# BACKPMAN30_Intfs.net
KiCad netlist of a schematic drawn in Altium Designer
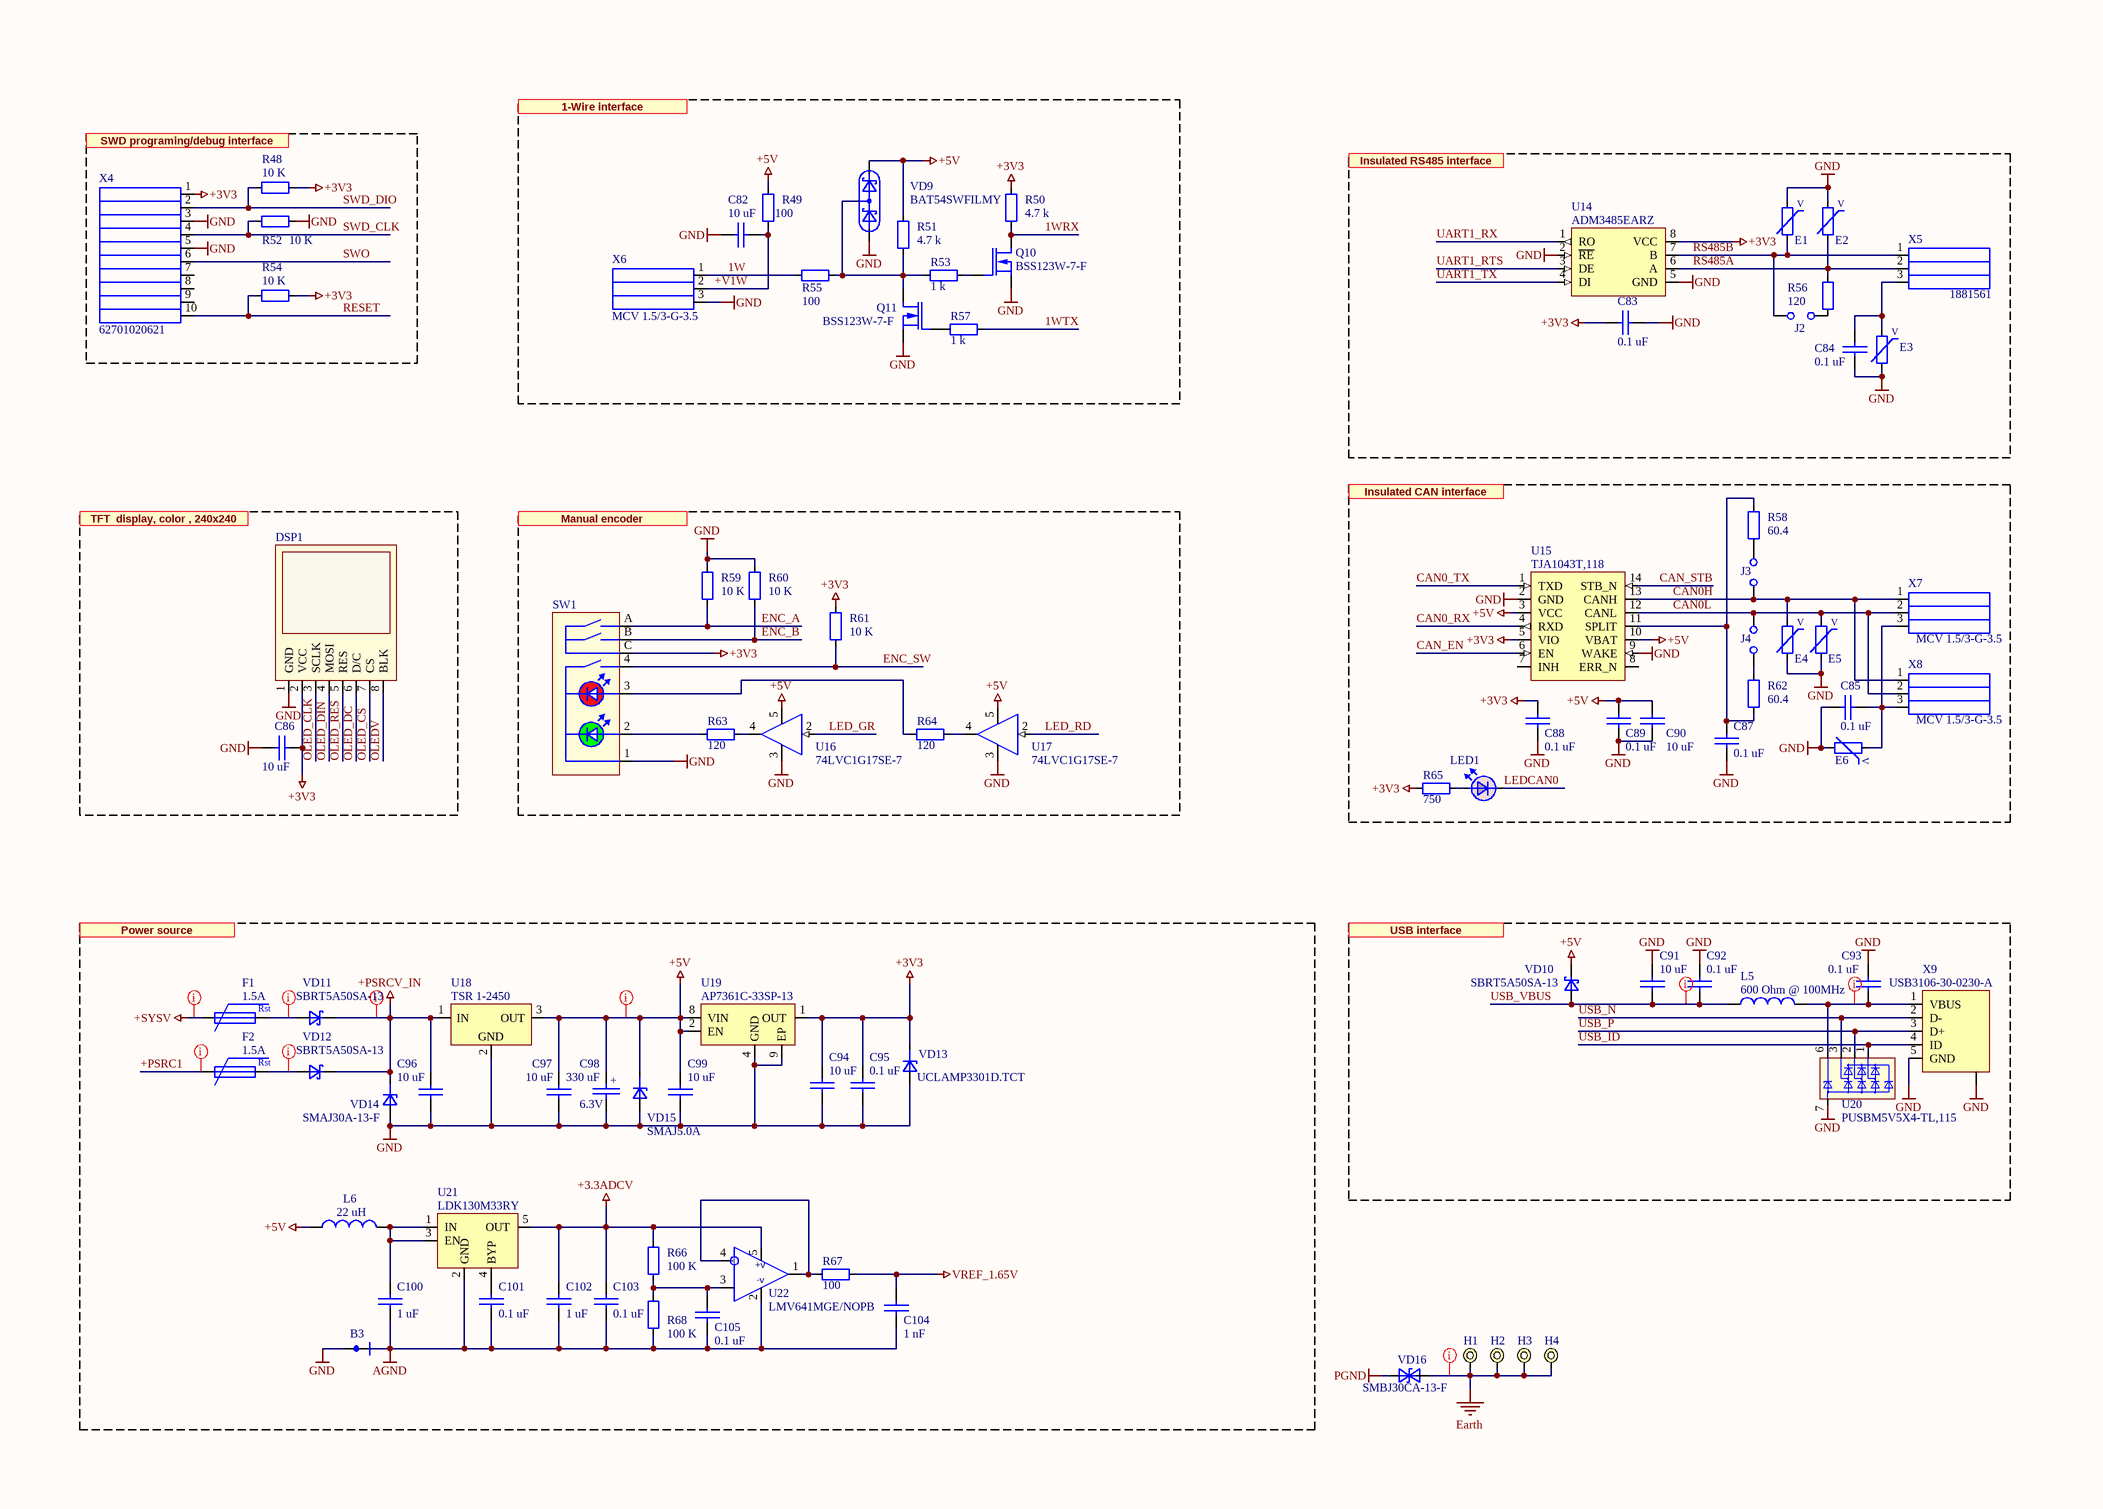
[diagram p0: BACKPMAN30_Intfs.SchDoc]

(export (version "E")
  (design (tool "Eeschema 10.0.6"))
  (components
    (comp (ref "B3")
      (value "Net tie 0.3mm")
      (footprint "Net tee 0.3 mm")
      (libsource (lib "ea_Mechanical") (part "Net tie 0.3mm"))
    )
    (comp (ref "C82")
      (value "10 uF")
      (footprint "2012[0805]")
      (description "10 µF ±10%, 25V, Ceramic Capacitor X5R 0805 (2012 Metric),  -55°C ~ 85°C")
      (fields (field (name "MANUFACTURER") "Murata Electronics") (field (name "TOLERANCE") "±10%"))
      (libsource (lib "ea_Capacitors_0805") (part "GRM21BR61E106KA73L"))
    )
    (comp (ref "C83")
      (value "0.1 uF")
      (footprint "1608[0603]")
      (description "0.1 µF ±10% 50V Ceramic Capacitor X7R 0603 (1608 Metric), -55°C ~ 125°C")
      (fields
        (field (name "MANUFACTURER") "Walsin Technology Corporation")
        (field (name "PARTNUM") "1292-1643-1-ND")
      )
      (libsource (lib "ea_Capacitors_0603") (part "0603B104K500CT"))
    )
    (comp (ref "C84")
      (value "0.1 uF")
      (footprint "1608[0603]")
      (description "0.1 µF ±10% 50V Ceramic Capacitor X7R 0603 (1608 Metric), -55°C ~ 125°C")
      (fields
        (field (name "TOLERANCE") "+-10%")
        (field (name "MANUFACTURER") "Walsin Technology Corporation")
      )
      (libsource (lib "ea_Capacitors_0603") (part "0603B104K500CT"))
    )
    (comp (ref "C85")
      (value "0.1 uF")
      (footprint "1608[0603]")
      (description "0.1 µF ±10% 50V Ceramic Capacitor X7R 0603 (1608 Metric), -55°C ~ 125°C")
      (fields
        (field (name "TOLERANCE") "+-10%")
        (field (name "MANUFACTURER") "Walsin Technology Corporation")
      )
      (libsource (lib "ea_Capacitors_0603") (part "0603B104K500CT"))
    )
    (comp (ref "C86")
      (value "10 uF")
      (footprint "2012[0805]")
      (description "10 µF ±10%, 25V, Ceramic Capacitor X5R 0805 (2012 Metric),  -55°C ~ 85°C")
      (fields (field (name "MANUFACTURER") "Murata Electronics") (field (name "TOLERANCE") "±10%"))
      (libsource (lib "ea_Capacitors_0805") (part "GRM21BR61E106KA73L"))
    )
    (comp (ref "C87")
      (value "0.1 uF")
      (footprint "1608[0603]")
      (description "0.1 µF ±10% 50V Ceramic Capacitor X7R 0603 (1608 Metric), -55°C ~ 125°C")
      (fields
        (field (name "TOLERANCE") "+-10%")
        (field (name "MANUFACTURER") "Walsin Technology Corporation")
      )
      (libsource (lib "ea_Capacitors_0603") (part "0603B104K500CT"))
    )
    (comp (ref "C88")
      (value "0.1 uF")
      (footprint "1608[0603]")
      (description "0.1 µF ±10% 50V Ceramic Capacitor X7R 0603 (1608 Metric), -55°C ~ 125°C")
      (fields
        (field (name "TOLERANCE") "+-10%")
        (field (name "MANUFACTURER") "Walsin Technology Corporation")
      )
      (libsource (lib "ea_Capacitors_0603") (part "0603B104K500CT"))
    )
    (comp (ref "C89")
      (value "0.1 uF")
      (footprint "1608[0603]")
      (description "0.1 µF ±10% 50V Ceramic Capacitor X7R 0603 (1608 Metric), -55°C ~ 125°C")
      (fields
        (field (name "TOLERANCE") "+-10%")
        (field (name "MANUFACTURER") "Walsin Technology Corporation")
      )
      (libsource (lib "ea_Capacitors_0603") (part "0603B104K500CT"))
    )
    (comp (ref "C90")
      (value "10 uF")
      (footprint "2012[0805]")
      (description "10 µF ±10%, 25V, Ceramic Capacitor X5R 0805 (2012 Metric),  -55°C ~ 85°C")
      (fields (field (name "MANUFACTURER") "Murata Electronics") (field (name "TOLERANCE") "±10%"))
      (libsource (lib "ea_Capacitors_0805") (part "GRM21BR61E106KA73L"))
    )
    (comp (ref "C91")
      (value "10 uF")
      (footprint "2012[0805]")
      (description "10 µF ±10%, 25V, Ceramic Capacitor X5R 0805 (2012 Metric),  -55°C ~ 85°C")
      (fields (field (name "MANUFACTURER") "Murata Electronics") (field (name "TOLERANCE") "±10%"))
      (libsource (lib "ea_Capacitors_0805") (part "GRM21BR61E106KA73L"))
    )
    (comp (ref "C92")
      (value "0.1 uF")
      (footprint "1608[0603]")
      (description "0.1 µF ±10% 50V Ceramic Capacitor X7R 0603 (1608 Metric), -55°C ~ 125°C")
      (fields
        (field (name "TOLERANCE") "+-10%")
        (field (name "MANUFACTURER") "Walsin Technology Corporation")
      )
      (libsource (lib "ea_Capacitors_0603") (part "0603B104K500CT"))
    )
    (comp (ref "C93")
      (value "0.1 uF")
      (footprint "1608[0603]")
      (description "0.1 µF ±10% 50V Ceramic Capacitor X7R 0603 (1608 Metric), -55°C ~ 125°C")
      (fields
        (field (name "TOLERANCE") "+-10%")
        (field (name "MANUFACTURER") "Walsin Technology Corporation")
      )
      (libsource (lib "ea_Capacitors_0603") (part "0603B104K500CT"))
    )
    (comp (ref "C94")
      (value "10 uF")
      (footprint "2012[0805]")
      (description "10 µF ±10%, 25V, Ceramic Capacitor X5R 0805 (2012 Metric),  -55°C ~ 85°C")
      (fields (field (name "MANUFACTURER") "Murata Electronics") (field (name "TOLERANCE") "±10%"))
      (libsource (lib "ea_Capacitors_0805") (part "GRM21BR61E106KA73L"))
    )
    (comp (ref "C95")
      (value "0.1 uF")
      (footprint "1608[0603]")
      (description "0.1 µF ±10% 50V Ceramic Capacitor X7R 0603 (1608 Metric), -55°C ~ 125°C")
      (fields
        (field (name "TOLERANCE") "+-10%")
        (field (name "MANUFACTURER") "Walsin Technology Corporation")
      )
      (libsource (lib "ea_Capacitors_0603") (part "0603B104K500CT"))
    )
    (comp (ref "C96")
      (value "10 uF")
      (footprint "3225[1210]")
      (description "10 µF ±10%, 50V, Ceramic Capacitor X7R, 1210 (3225 Metric), -55°C ~ 125°C")
      (fields
        (field (name "MANUFACTURER") "CAL-CHIP ELECTRONICS, INC.")
        (field (name "PARTNUM") "2571-GMC32X7R106K50NTTR-ND")
      )
      (libsource (lib "ea_Capacitors_1210") (part "GMC32X7R106K50NT"))
    )
    (comp (ref "C97")
      (value "10 uF")
      (footprint "2012[0805]")
      (description "10 µF ±10%, 25V, Ceramic Capacitor X5R 0805 (2012 Metric),  -55°C ~ 85°C")
      (fields (field (name "MANUFACTURER") "Murata Electronics") (field (name "TOLERANCE") "±10%"))
      (libsource (lib "ea_Capacitors_0805") (part "GRM21BR61E106KA73L"))
    )
    (comp (ref "C98")
      (value "330 uF")
      (footprint "T495 D")
      (description "330 µF Molded Tantalum Capacitors 6.3 V 2917 (7343 Metric) 100mOhm, -55°C ~ 125°C")
      (fields
        (field (name "MANUFACTURER") "KEMET")
        (field (name "TOLERANCE") "±10%")
        (field (name "VOLTAGE") "6.3V")
      )
      (libsource (lib "ea_Capacitors") (part "T495D337K006ATE100"))
    )
    (comp (ref "C99")
      (value "10 uF")
      (footprint "2012[0805]")
      (description "10 µF ±10%, 25V, Ceramic Capacitor X5R 0805 (2012 Metric),  -55°C ~ 85°C")
      (fields (field (name "MANUFACTURER") "Murata Electronics") (field (name "TOLERANCE") "±10%"))
      (libsource (lib "ea_Capacitors_0805") (part "GRM21BR61E106KA73L"))
    )
    (comp (ref "C100")
      (value "1 uF")
      (footprint "1608[0603]")
      (description "1 uF, ±10%, Low ESL, 50V, Ceramic Capacitor X5R 0603 (1608 Metric), -55°C ~ 85°C")
      (fields (field (name "MANUFACTURER") "Venkel") (field (name "PARTNUM") "445-7468-1-ND"))
      (libsource (lib "ea_Capacitors_0603") (part "C1608X5R1H105K080AB"))
    )
    (comp (ref "C101")
      (value "0.1 uF")
      (footprint "1608[0603]")
      (description "0.1 µF ±10% 50V Ceramic Capacitor X7R 0603 (1608 Metric), -55°C ~ 125°C")
      (fields
        (field (name "MANUFACTURER") "Walsin Technology Corporation")
        (field (name "PARTNUM") "1292-1643-1-ND")
      )
      (libsource (lib "ea_Capacitors_0603") (part "0603B104K500CT"))
    )
    (comp (ref "C102")
      (value "1 uF")
      (footprint "1608[0603]")
      (description "1 uF, ±10%, Low ESL, 50V, Ceramic Capacitor X5R 0603 (1608 Metric), -55°C ~ 85°C")
      (fields (field (name "MANUFACTURER") "Venkel") (field (name "PARTNUM") "445-7468-1-ND"))
      (libsource (lib "ea_Capacitors_0603") (part "C1608X5R1H105K080AB"))
    )
    (comp (ref "C103")
      (value "0.1 uF")
      (footprint "1608[0603]")
      (description "0.1 µF ±10% 50V Ceramic Capacitor X7R 0603 (1608 Metric), -55°C ~ 125°C")
      (fields
        (field (name "MANUFACTURER") "Walsin Technology Corporation")
        (field (name "PARTNUM") "1292-1643-1-ND")
      )
      (libsource (lib "ea_Capacitors_0603") (part "0603B104K500CT"))
    )
    (comp (ref "C104")
      (value "1 nF")
      (footprint "0603 CAP")
      (description "1000pF, ±5%, 50V, X7R, 0603 (1608 Metric), -55°C ~ 125°C, -, General Purpose")
      (fields (field (name "PART NUMBER") "CC0603JRX7R9BB102") (field (name "MANUFACTURER") "Yageo"))
      (libsource (lib "ea_PassivComps") (part "Capacitor"))
    )
    (comp (ref "C105")
      (value "0.1 uF")
      (footprint "1608[0603]")
      (description "0.1 µF ±10% 50V Ceramic Capacitor X7R 0603 (1608 Metric), -55°C ~ 125°C")
      (fields
        (field (name "MANUFACTURER") "Walsin Technology Corporation")
        (field (name "PARTNUM") "1292-1643-1-ND")
      )
      (libsource (lib "ea_Capacitors_0603") (part "0603B104K500CT"))
    )
    (comp (ref "DSP1")
      (value "1.54_inch_IPS_Module")
      (footprint "1.54 inch IPS 240x240")
      (fields (field (name "PARTNUM") "MSP1541"))
      (libsource (lib "ea_LCD") (part "1.54_inch_IPS_Module"))
    )
    (comp (ref "E1")
      (value "ESD03A5V5R17V")
      (footprint "0603")
      (description "Low and Ultra Low Capacitance ESD Suppressor, Voperating=5.5V, Vclamp=17V, < 1nS,1nA, 0603,")
      (fields
        (field (name "MANUFACTURER") "Stackpole Electronics Inc")
        (field (name "PARTNUM") "ESD03A5V5R17VCT-ND")
      )
      (libsource (lib "") (part "ESD03A5V5R17V_1"))
    )
    (comp (ref "E2")
      (value "ESD03A5V5R17V")
      (footprint "0603")
      (description "Low and Ultra Low Capacitance ESD Suppressor, Voperating=5.5V, Vclamp=17V, < 1nS,1nA, 0603,")
      (fields
        (field (name "MANUFACTURER") "Stackpole Electronics Inc")
        (field (name "PARTNUM") "ESD03A5V5R17VCT-ND")
      )
      (libsource (lib "") (part "ESD03A5V5R17V_1"))
    )
    (comp (ref "E3")
      (value "823 560 505 60")
      (footprint "0603")
      (description "Low and Ultra Low Capacitance ESD Suppressor, Voperating=5.5V, Vclamp=17V, < 1nS,1nA, 0603,")
      (fields
        (field (name "MANUFACTURER") "Stackpole Electronics Inc")
        (field (name "PARTNUM") "ESD03A5V5R17VCT-ND")
      )
      (libsource (lib "") (part "ESD03A5V5R17V_1"))
    )
    (comp (ref "E4")
      (value "ESD03A5V5R17V")
      (footprint "0603")
      (description "Low and Ultra Low Capacitance ESD Suppressor, Voperating=5.5V, Vclamp=17V, < 1nS,1nA, 0603,")
      (fields
        (field (name "MANUFACTURER") "Stackpole Electronics Inc")
        (field (name "PARTNUM") "ESD03A5V5R17VCT-ND")
      )
      (libsource (lib "") (part "ESD03A5V5R17V_1"))
    )
    (comp (ref "E5")
      (value "ESD03A5V5R17V")
      (footprint "0603")
      (description "Low and Ultra Low Capacitance ESD Suppressor, Voperating=5.5V, Vclamp=17V, < 1nS,1nA, 0603,")
      (fields
        (field (name "MANUFACTURER") "Stackpole Electronics Inc")
        (field (name "PARTNUM") "ESD03A5V5R17VCT-ND")
      )
      (libsource (lib "") (part "ESD03A5V5R17V_1"))
    )
    (comp (ref "E6")
      (value "ESD03A5V5R17V")
      (footprint "0603")
      (description "Low and Ultra Low Capacitance ESD Suppressor, Voperating=5.5V, Vclamp=17V, < 1nS,1nA, 0603,")
      (fields
        (field (name "MANUFACTURER") "Stackpole Electronics Inc")
        (field (name "PARTNUM") "ESD03A5V5R17VCT-ND")
      )
      (libsource (lib "ea_TVS_protection") (part "ESD03A5V5R17V"))
    )
    (comp (ref "F1")
      (value "1.5A")
      (footprint "2920 (7351 Metric)")
      (description "PTC RESETTABLE 60V 750MA, It=1.5A, 0.3s 2920(7351)")
      (fields (field (name "MANUFACTURER") "Bel Fuse Inc.") (field (name "PARTNUM") "507-1743-1-ND"))
      (libsource (lib "ea_Fuses") (part "0ZCF0075AF2C"))
    )
    (comp (ref "F2")
      (value "1.5A")
      (footprint "2920 (7351 Metric)")
      (description "PTC RESETTABLE 60V 750MA, It=1.5A, 0.3s 2920(7351)")
      (fields (field (name "MANUFACTURER") "Bel Fuse Inc.") (field (name "PARTNUM") "507-1743-1-ND"))
      (libsource (lib "ea_Fuses") (part "0ZCF0075AF2C"))
    )
    (comp (ref "H1")
      (value "Hole 5MM Plated")
      (footprint "HOLE_5MM plated")
      (libsource (lib "ea_Mechanical") (part "Hole 5MM Plated"))
    )
    (comp (ref "H2")
      (value "Hole 5MM Plated")
      (footprint "HOLE_5MM plated")
      (libsource (lib "ea_Mechanical") (part "Hole 5MM Plated"))
    )
    (comp (ref "H3")
      (value "Hole 5MM Plated")
      (footprint "HOLE_5MM plated")
      (libsource (lib "ea_Mechanical") (part "Hole 5MM Plated"))
    )
    (comp (ref "H4")
      (value "Hole 5MM Plated")
      (footprint "HOLE_5MM plated")
      (libsource (lib "ea_Mechanical") (part "Hole 5MM Plated"))
    )
    (comp (ref "J2")
      (value "PH1-02-TA-HT")
      (footprint "HDR1X2V")
      (description "Connector Header Through Hole 2 position 0.100\" (2.54mm), Contact Length - Mating 6 mm")
      (fields (field (name "MANUFACTURER") "Adam Tech") (field (name "PARTNUM") "2057-PH1-02-UA-ND"))
      (libsource (lib "ea_Commutation") (part "PH1-02-UA"))
    )
    (comp (ref "J3")
      (value "PH1-02-TA-HT")
      (footprint "HDR1X2V")
      (description "Connector Header Through Hole 2 position 0.100\" (2.54mm), Contact Length - Mating 6 mm")
      (fields (field (name "MANUFACTURER") "Adam Tech") (field (name "PARTNUM") "2057-PH1-02-UA-ND"))
      (libsource (lib "ea_Commutation") (part "PH1-02-UA"))
    )
    (comp (ref "J4")
      (value "PH1-02-TA-HT")
      (footprint "HDR1X2V")
      (description "Connector Header Through Hole 2 position 0.100\" (2.54mm), Contact Length - Mating 6 mm")
      (fields (field (name "MANUFACTURER") "Adam Tech") (field (name "PARTNUM") "2057-PH1-02-UA-ND"))
      (libsource (lib "ea_Commutation") (part "PH1-02-UA"))
    )
    (comp (ref "L5")
      (value "600 Ohm @ 100MHz")
      (footprint "0805")
      (description "FERRITE BEAD 600 OHM, 0805, -55°C ~ 125°C")
      (fields (field (name "MANUFACTURER") "TDK Corporation") (field (name "PARTNUM") "445-2206-1-ND"))
      (libsource (lib "ea_Inductors") (part "MPZ2012S601AT000"))
    )
    (comp (ref "L6")
      (value "22 uH")
      (footprint "2518")
      (description "22 µH Unshielded Wirewound Inductor, 490 mA, 560mOhm, 1007 (2518 Metric)")
      (fields (field (name "MANUFACTURER") "Taiyo Yuden") (field (name "PARTNUM") "587-2439-1-ND"))
      (libsource (lib "ea_Inductors") (part "BRC2518T220K"))
    )
    (comp (ref "LED1")
      (value "SML-211UTT86")
      (footprint "0805 LED")
      (description "0805 red LED, hibright, 2 mA, 1.8V, 130°")
      (fields (field (name "MANUFACTURER") "Rohm") (field (name "PARTNUM") "511-1292-1-ND"))
      (libsource (lib "ea_Indicators") (part "SML-211UTT86"))
    )
    (comp (ref "Q10")
      (value "BSS123W-7-F")
      (footprint "SOT323-3")
      (description "MOSFETs N-CH, 2V @ 1mA, 6 Ohm @ 170mA, 10V, 170mA, 100V, SOT-323,  -55°C ~ 150°C")
      (fields (field (name "MANUFACTURER") "Diodes Incorporated") (field (name "PARTNUM") "BSS123W-FDICT-ND"))
      (libsource (lib "") (part "BSS123W-7-F_1"))
    )
    (comp (ref "Q11")
      (value "BSS123W-7-F")
      (footprint "SOT323-3")
      (description "MOSFETs N-CH, 2V @ 1mA, 6 Ohm @ 170mA, 10V, 170mA, 100V, SOT-323,  -55°C ~ 150°C")
      (fields (field (name "MANUFACTURER") "Diodes Incorporated") (field (name "PARTNUM") "BSS123W-FDICT-ND"))
      (libsource (lib "ea_Transistors") (part "BSS123W-7-F"))
    )
    (comp (ref "R48")
      (value "10 K")
      (footprint "0603")
      (fields
        (field (name "MANUFACTURER") "Stackpole Electronics Inc")
        (field (name "TOLERANCE") "1%")
        (field (name "PARTNUM") "RMCF0603FT10K0CT-ND")
      )
      (libsource (lib "ea_Resistors_0603") (part "RMCF0603FT10K0"))
    )
    (comp (ref "R49")
      (value "100")
      (footprint "0603")
      (fields
        (field (name "MANUFACTURER") "Stackpole Electronics Inc.")
        (field (name "TOLERANCE") "±1%")
        (field (name "VOLTAGE") "75V")
      )
      (libsource (lib "ea_PassivComps") (part "Resistor"))
    )
    (comp (ref "R50")
      (value "4.7 k")
      (footprint "0603")
      (fields
        (field (name "MANUFACTURER") "Stackpole Electronics Inc.")
        (field (name "TOLERANCE") "±1%")
        (field (name "VOLTAGE") "75V")
      )
      (libsource (lib "") (part "Resistor_1"))
    )
    (comp (ref "R51")
      (value "4.7 k")
      (footprint "0603")
      (fields
        (field (name "MANUFACTURER") "Stackpole Electronics Inc.")
        (field (name "TOLERANCE") "±1%")
        (field (name "VOLTAGE") "75V")
      )
      (libsource (lib "") (part "Resistor_1"))
    )
    (comp (ref "R52")
      (value "10 K")
      (footprint "0603")
      (fields
        (field (name "MANUFACTURER") "Stackpole Electronics Inc")
        (field (name "TOLERANCE") "1%")
        (field (name "PARTNUM") "RMCF0603FT10K0CT-ND")
      )
      (libsource (lib "ea_Resistors_0603") (part "RMCF0603FT10K0"))
    )
    (comp (ref "R53")
      (value "1 k")
      (footprint "0603")
      (fields
        (field (name "MANUFACTURER") "Stackpole Electronics Inc.")
        (field (name "TOLERANCE") "±1%")
        (field (name "VOLTAGE") "75V")
      )
      (libsource (lib "") (part "Resistor_2"))
    )
    (comp (ref "R54")
      (value "10 K")
      (footprint "0603")
      (fields
        (field (name "MANUFACTURER") "Stackpole Electronics Inc")
        (field (name "TOLERANCE") "1%")
        (field (name "PARTNUM") "RMCF0603FT10K0CT-ND")
      )
      (libsource (lib "ea_Resistors_0603") (part "RMCF0603FT10K0"))
    )
    (comp (ref "R55")
      (value "100")
      (footprint "0603")
      (fields
        (field (name "MANUFACTURER") "Stackpole Electronics Inc.")
        (field (name "TOLERANCE") "±1%")
        (field (name "VOLTAGE") "75V")
      )
      (libsource (lib "") (part "Resistor_3"))
    )
    (comp (ref "R56")
      (value "120")
      (footprint "0603")
      (fields
        (field (name "MANUFACTURER") "Stackpole Electronics Inc.")
        (field (name "TOLERANCE") "±1%")
        (field (name "VOLTAGE") "75V")
      )
      (libsource (lib "ea_PassivComps") (part "Resistor"))
    )
    (comp (ref "R57")
      (value "1 k")
      (footprint "0603")
      (fields
        (field (name "MANUFACTURER") "Stackpole Electronics Inc.")
        (field (name "TOLERANCE") "±1%")
        (field (name "VOLTAGE") "75V")
      )
      (libsource (lib "") (part "Resistor_2"))
    )
    (comp (ref "R58")
      (value "60.4")
      (footprint "0603")
      (fields
        (field (name "MANUFACTURER") "Vishay Dale")
        (field (name "TOLERANCE") "±1%")
        (field (name "VOLTAGE") "75V")
      )
      (libsource (lib "ea_PassivComps") (part "Resistor"))
    )
    (comp (ref "R59")
      (value "10 K")
      (footprint "0603")
      (fields
        (field (name "MANUFACTURER") "Stackpole Electronics Inc")
        (field (name "TOLERANCE") "1%")
        (field (name "PARTNUM") "RMCF0603FT10K0CT-ND")
      )
      (libsource (lib "") (part "RMCF0603FT10K0_1"))
    )
    (comp (ref "R60")
      (value "10 K")
      (footprint "0603")
      (fields
        (field (name "MANUFACTURER") "Stackpole Electronics Inc")
        (field (name "TOLERANCE") "1%")
        (field (name "PARTNUM") "RMCF0603FT10K0CT-ND")
      )
      (libsource (lib "") (part "RMCF0603FT10K0_1"))
    )
    (comp (ref "R61")
      (value "10 K")
      (footprint "0603")
      (fields
        (field (name "MANUFACTURER") "Stackpole Electronics Inc")
        (field (name "TOLERANCE") "1%")
        (field (name "PARTNUM") "RMCF0603FT10K0CT-ND")
      )
      (libsource (lib "") (part "RMCF0603FT10K0_1"))
    )
    (comp (ref "R62")
      (value "60.4")
      (footprint "0603")
      (fields
        (field (name "MANUFACTURER") "Vishay Dale")
        (field (name "TOLERANCE") "±1%")
        (field (name "VOLTAGE") "75V")
      )
      (libsource (lib "ea_PassivComps") (part "Resistor"))
    )
    (comp (ref "R63")
      (value "120")
      (footprint "0603")
      (fields
        (field (name "MANUFACTURER") "Stackpole Electronics Inc.")
        (field (name "TOLERANCE") "±1%")
        (field (name "VOLTAGE") "75V")
      )
      (libsource (lib "") (part "Resistor_2"))
    )
    (comp (ref "R64")
      (value "120")
      (footprint "0603")
      (fields
        (field (name "MANUFACTURER") "Stackpole Electronics Inc.")
        (field (name "TOLERANCE") "±1%")
        (field (name "VOLTAGE") "75V")
      )
      (libsource (lib "") (part "Resistor_2"))
    )
    (comp (ref "R65")
      (value "750")
      (footprint "0603")
      (fields
        (field (name "MANUFACTURER") "Stackpole Electronics Inc.")
        (field (name "TOLERANCE") "±1%")
        (field (name "VOLTAGE") "75V")
      )
      (libsource (lib "") (part "Resistor_2"))
    )
    (comp (ref "R66")
      (value "100 K")
      (footprint "0603")
      (fields
        (field (name "MANUFACTURER") "Susumu")
        (field (name "TOLERANCE") "±0.05%")
        (field (name "PARTNUM") "RG16N100KWCT-ND")
      )
      (libsource (lib "ea_Resistors_0603") (part "RG1608N-104-W-T1"))
    )
    (comp (ref "R67")
      (value "100")
      (footprint "0603")
      (fields
        (field (name "MANUFACTURER") "Stackpole Electronics Inc.")
        (field (name "TOLERANCE") "±1%")
        (field (name "VOLTAGE") "75V")
      )
      (libsource (lib "") (part "Resistor_2"))
    )
    (comp (ref "R68")
      (value "100 K")
      (footprint "0603")
      (fields
        (field (name "MANUFACTURER") "Susumu")
        (field (name "TOLERANCE") "±0.05%")
        (field (name "PARTNUM") "RG16N100KWCT-ND")
      )
      (libsource (lib "ea_Resistors_0603") (part "RG1608N-104-W-T1"))
    )
    (comp (ref "SW1")
      (value "PEL12D-4225S-S2024")
      (footprint "PEL12D-4225S-S2024")
      (description "Rotary Encoder Mechanical 24 Quadrature (Incremental) Vertical")
      (fields (field (name "MANUFACTURER") "Bourns Inc.") (field (name "PARTNUM") "PEL12D-4225S-S2024-ND"))
      (libsource (lib "ea_Commutation") (part "PEL12D-4225S-S2024"))
    )
    (comp (ref "U14")
      (value "ADM3485EARZ")
      (footprint "SO-8")
      (description "1/1 Transceiver Half RS422, RS485, VCC 3.3 V,  8-SOIC, -40°C ~ 85°C")
      (fields (field (name "MANUFACTURER") "Analog Devices") (field (name "PARTNUM") "584-ADM3485EARZ-R7"))
      (libsource (lib "ea_IC_Interfaces") (part "ADM3485EARZ"))
    )
    (comp (ref "U15")
      (value "TJA1043T,118")
      (footprint "SOT108-1")
      (description "1/1 Transceiver Half CANbus, 5Mbps, 4.5-5.5V, 3V IO,  14-SO, -40°C ~ 150°C")
      (fields (field (name "MANUFACTURER") "NXP") (field (name "PARTNUM") "2776120RL"))
      (libsource (lib "ea_IC_Interfaces") (part "TJA1043T,118"))
    )
    (comp (ref "U16")
      (value "74LVC1G17SE-7")
      (footprint "SOT-353 ON Semi")
      (description "IC SGL SCHMITT BUFFER SOT353")
      (fields
        (field (name "MANUFACTURER") "Diodes Incorporated")
        (field (name "PARTNUM") "74LVC1G17SE-7CT-ND")
      )
      (libsource (lib "ea_IC_Logic") (part "74LVC1G17SE-7"))
    )
    (comp (ref "U17")
      (value "74LVC1G17SE-7")
      (footprint "SOT-353 ON Semi")
      (description "IC SGL SCHMITT BUFFER SOT353")
      (fields
        (field (name "MANUFACTURER") "Diodes Incorporated")
        (field (name "PARTNUM") "74LVC1G17SE-7CT-ND")
      )
      (libsource (lib "ea_IC_Logic") (part "74LVC1G17SE-7"))
    )
    (comp (ref "U18")
      (value "TSR 1-2450")
      (footprint "TSR 1 Traco Power")
      (description "Linear Regulator Replacement DC DC Converter 5W, 5V, 1A, 6.5V - 36V Input, -40°C ~ 85°C")
      (fields (field (name "MANUFACTURER") "Traco Power") (field (name "PARTNUM") "1951-2747-ND"))
      (libsource (lib "ea_IC_Power_Reg_Ref_Sw") (part "TSR 1-2450"))
    )
    (comp (ref "U19")
      (value "AP7361C-33SP-13")
      (footprint "SOIC-8 EDP")
      (description "LDO, 3.3 V, 1A, 0.36V@1A, Vin=6V max, -40..+85C, 8-SO-EP")
      (fields
        (field (name "PARTNUM") "AP7361C-33SP-13DICT-ND")
        (field (name "MANUFACTURER") "Diodes Incorporated")
      )
      (libsource (lib "ea_IC_Power_Reg_Ref_Sw") (part "AP7361C-33SP-13"))
    )
    (comp (ref "U20")
      (value "PUSBM5V5X4-TL,115")
      (footprint "DFN1616-6")
      (description "TVS DIODE 5.5VWM 12VC 6HXSON")
      (fields (field (name "MANUFACTURER") "NXP Semiconductors") (field (name "PARTNUM") "568-10921-1-ND"))
      (libsource (lib "ea_TVS_protection") (part "PUSBM5V5X4-TL,115"))
    )
    (comp (ref "U21")
      (value "LDK130M33RY")
      (footprint "SOT23-5")
      (description "LDO 3.3 V, 250 mA, Vin < 5.5V, Iq < 12uA, -40..+125 C, SOT23-5")
      (fields (field (name "MANUFACTURER") "STMicroelectronics") (field (name "PARTNUM") "511-LDK130M33RY"))
      (libsource (lib "ea_IC_Power_Reg_Ref_Sw") (part "LDK130M33RY"))
    )
    (comp (ref "U22")
      (value "LMV641MGE/NOPB")
      (footprint "SOT-353 ON Semi")
      (description "OpAmp,  Rail-to-Rail,  10MHz, VSS 2.7V ~ 12V, Vofs 30µV,  SC-70-5, -40°C ~ 125°C")
      (fields
        (field (name "MANUFACTURER") "Texas Instruments")
        (field (name "PARTNUM") "LMV641MGE/NOPBCT-ND")
      )
      (libsource (lib "ea_IC_OPAmps_AnComparators") (part "LMV641MGE/NOPB"))
    )
    (comp (ref "VD9")
      (value "BAT54SWFILMY")
      (footprint "SOT323-3")
      (description "Series Shottky Diodes array, 40V, 300 mA, SOT-323, -40°C...150°C")
      (fields (field (name "MANUFACTURER") "STMicroelectronics") (field (name "PARTNUM") "497-17757-1-ND"))
      (libsource (lib "ea_Diodes") (part "BAT54SWFILMY"))
    )
    (comp (ref "VD10")
      (value "SBRT5A50SA-13")
      (footprint "SMA")
      (description "Schottky Power Rectifier 3A, 40V, SMA")
      (fields
        (field (name "MANUFACTURER") "Diodes Incorporated")
        (field (name "PARTNUM") "SBRT5A50SA-13DICT-ND")
      )
      (libsource (lib "ea_Diodes") (part "SBRT5A50SA-13"))
    )
    (comp (ref "VD11")
      (value "SBRT5A50SA-13")
      (footprint "SMA")
      (description "Schottky Power Rectifier 3A, 40V, SMA")
      (fields
        (field (name "MANUFACTURER") "Diodes Incorporated")
        (field (name "PARTNUM") "SBRT5A50SA-13DICT-ND")
      )
      (libsource (lib "ea_Diodes") (part "SBRT5A50SA-13"))
    )
    (comp (ref "VD12")
      (value "SBRT5A50SA-13")
      (footprint "SMA")
      (description "Schottky Power Rectifier 3A, 40V, SMA")
      (fields
        (field (name "MANUFACTURER") "Diodes Incorporated")
        (field (name "PARTNUM") "SBRT5A50SA-13DICT-ND")
      )
      (libsource (lib "ea_Diodes") (part "SBRT5A50SA-13"))
    )
    (comp (ref "VD13")
      (value "UCLAMP3301D.TCT")
      (footprint "SOD-323")
      (description "TVS 3.3V (Max), Vbr=3.5V, 9.5V Clamp 10A (8/20µs) Ipp Tvs Diode Surface Mount SOD-323")
      (fields (field (name "MANUFACTURER") "Semtech Corporation") (field (name "PARTNUM") "UCLAMP3301DCT-ND"))
      (libsource (lib "ea_TVS_protection") (part "UCLAMP3301D.TCT"))
    )
    (comp (ref "VD14")
      (value "SMAJ30A-13-F")
      (footprint "SMA")
      (description "48.4V Clamp 8.3A Ipp Tvs Diode Surface Mount SMA,")
      (fields (field (name "MANUFACTURER") "Diodes Incorporated") (field (name "PARTNUM") "SMAJ30A-FDICT-ND"))
      (libsource (lib "ea_TVS_protection") (part "SMAJ30A-13-F"))
    )
    (comp (ref "VD15")
      (value "SMAJ5.0A")
      (footprint "SMA")
      (description "9.2V Clamp 43.5A Ipp Tvs Diode Surface Mount SMA, -55°C ~ 150°C (TJ)")
      (fields (field (name "MANUFACTURER") "Littelfuse Inc.") (field (name "PARTNUM") "SMAJ5.0ALFCT-ND"))
      (libsource (lib "ea_TVS_protection") (part "SMAJ5.0A"))
    )
    (comp (ref "VD16")
      (value "SMBJ30CA-13-F")
      (footprint "DO-214AA_SMBJ BI")
      (description "TVS 600W, Vbr=33.3V, Vcl=48.4V,  Bidirectional, SMB, -55°C ~ 150°C")
      (fields
        (field (name "MANUFACTURER") "Diodes Incorporated")
        (field (name "PARTNUM") "SMBJ30CA-FDICT-ND")
      )
      (libsource (lib "ea_TVS_protection") (part "SMBJ30CA-13-F"))
    )
    (comp (ref "X4")
      (value "62701020621")
      (footprint "SHF-105-01-L-D-SM")
      (description "10 Positions Header Connector 0.050\" (1.27mm) Surface Mount Gold")
      (fields (field (name "MANUFACTURER") "Wurth"))
      (libsource (lib "ea_Connectors_1.27_mm_pitch") (part "62701020621"))
    )
    (comp (ref "X5")
      (value "1881561")
      (footprint "1881561")
      (description "Printed-circuit board connector - MCV 0,5/ 3-G-2,5 - 1881561")
      (fields (field (name "MANUFACTURER") "Phoenix Contact"))
      (libsource (lib "ea_Connectors_2.5_mm_pitch") (part "1881561"))
    )
    (comp (ref "X6")
      (value "MCV 1.5/3-G-3.5")
      (footprint "mcv1.5-3-g_3.5 green + MC 1,5 3-ST-3,5 - 1840379")
      (description "HEADER, VERTICAL, 3.5MM, 3WAY")
      (fields (field (name "MANUFACTURER") "PHOENIX CONTACT") (field (name "PARTNUM") "1843619"))
      (libsource (lib "ea_PhoenixContacts") (part "MCV 1.5/3-G-3.5"))
    )
    (comp (ref "X7")
      (value "MCV 1.5/3-G-3.5")
      (footprint "mcv1.5-3-g_3.5 green + MC 1,5 3-ST-3,5 - 1840379")
      (description "HEADER, VERTICAL, 3.5MM, 3WAY")
      (fields (field (name "MANUFACTURER") "PHOENIX CONTACT") (field (name "PARTNUM") "1843619"))
      (libsource (lib "ea_PhoenixContacts") (part "MCV 1.5/3-G-3.5"))
    )
    (comp (ref "X8")
      (value "MCV 1.5/3-G-3.5")
      (footprint "mcv1.5-3-g_3.5 green + MC 1,5 3-ST-3,5 - 1840379")
      (description "HEADER, VERTICAL, 3.5MM, 3WAY")
      (fields (field (name "MANUFACTURER") "PHOENIX CONTACT") (field (name "PARTNUM") "1843619"))
      (libsource (lib "ea_PhoenixContacts") (part "MCV 1.5/3-G-3.5"))
    )
    (comp (ref "X9")
      (value "USB3106-30-0230-A")
      (footprint "USB3106-30-0230-A")
      (description "USB - micro AB USB 2.0 Receptacle Connector 5 Position Through Hole")
      (fields (field (name "MANUFACTURER") "GCT") (field (name "PARTNUM") "2073-USB3106-30-0230-ACT-ND"))
      (libsource (lib "ea_Connectors_USB") (part "USB3106-30-0230-A"))
    )
  )
  (nets
    (net (code "1") (name "+3.3ADCV") (class "Default")
      (node (ref "C102") (pin "2") (pinfunction "2_2") (pintype "passive"))
      (node (ref "C103") (pin "1") (pinfunction "1_1") (pintype "passive"))
      (node (ref "R66") (pin "2") (pinfunction "2_2") (pintype "passive"))
      (node (ref "U21") (pin "5") (pinfunction "OUT_5") (pintype "power_in"))
      (node (ref "U22") (pin "5") (pinfunction "V+_5") (pintype "power_in"))
    )
    (net (code "2") (name "+3V3") (class "Default")
      (node (ref "C83") (pin "1") (pinfunction "1_1") (pintype "passive"))
      (node (ref "C86") (pin "2") (pinfunction "2_2") (pintype "passive"))
      (node (ref "C88") (pin "2") (pinfunction "2_2") (pintype "passive"))
      (node (ref "C94") (pin "2") (pinfunction "2_2") (pintype "passive"))
      (node (ref "C95") (pin "2") (pinfunction "2_2") (pintype "passive"))
      (node (ref "DSP1") (pin "2") (pinfunction "VCC_2") (pintype "passive"))
      (node (ref "R48") (pin "2") (pinfunction "2_2") (pintype "passive"))
      (node (ref "R50") (pin "1") (pinfunction "1_1") (pintype "passive"))
      (node (ref "R54") (pin "2") (pinfunction "2_2") (pintype "passive"))
      (node (ref "R61") (pin "2") (pinfunction "2_2") (pintype "passive"))
      (node (ref "R65") (pin "2") (pinfunction "2_2") (pintype "passive"))
      (node (ref "SW1") (pin "C") (pinfunction "C_C") (pintype "passive"))
      (node (ref "U14") (pin "8") (pinfunction "VCC_8") (pintype "power_in"))
      (node (ref "U15") (pin "5") (pinfunction "VIO_5") (pintype "power_in"))
      (node (ref "U19") (pin "1") (pinfunction "OUT_1") (pintype "passive"))
      (node (ref "VD13") (pin "1") (pinfunction "C_1") (pintype "passive"))
      (node (ref "X4") (pin "1") (pinfunction "1_1") (pintype "passive"))
    )
    (net (code "3") (name "+5V") (class "Default")
      (node (ref "C89") (pin "2") (pinfunction "2_2") (pintype "passive"))
      (node (ref "C90") (pin "2") (pinfunction "2_2") (pintype "passive"))
      (node (ref "C97") (pin "2") (pinfunction "2_2") (pintype "passive"))
      (node (ref "C98") (pin "1") (pinfunction "1_1") (pintype "passive"))
      (node (ref "C99") (pin "2") (pinfunction "2_2") (pintype "passive"))
      (node (ref "L6") (pin "1") (pinfunction "1_1") (pintype "passive"))
      (node (ref "R49") (pin "2") (pinfunction "2_2") (pintype "passive"))
      (node (ref "R51") (pin "1") (pinfunction "1_1") (pintype "passive"))
      (node (ref "U15") (pin "10") (pinfunction "VBAT_10") (pintype "power_in"))
      (node (ref "U15") (pin "3") (pinfunction "VCC_3") (pintype "power_in"))
      (node (ref "U16") (pin "5") (pinfunction "VCC_5") (pintype "power_in"))
      (node (ref "U17") (pin "5") (pinfunction "VCC_5") (pintype "power_in"))
      (node (ref "U18") (pin "3") (pinfunction "OUT_3") (pintype "power_in"))
      (node (ref "U19") (pin "2") (pinfunction "EN_2") (pintype "passive"))
      (node (ref "U19") (pin "8") (pinfunction "VIN_8") (pintype "passive"))
      (node (ref "VD10") (pin "1") (pinfunction "1_1") (pintype "passive"))
      (node (ref "VD15") (pin "1") (pinfunction "1_1") (pintype "passive"))
      (node (ref "VD9") (pin "2") (pinfunction "2_2") (pintype "passive"))
    )
    (net (code "4") (name "+PSRCV_IN") (class "Default")
      (node (ref "C96") (pin "1") (pinfunction "1_1") (pintype "passive"))
      (node (ref "U18") (pin "1") (pinfunction "IN_1") (pintype "power_in"))
      (node (ref "VD11") (pin "1") (pinfunction "1_1") (pintype "passive"))
      (node (ref "VD12") (pin "1") (pinfunction "1_1") (pintype "passive"))
      (node (ref "VD14") (pin "1") (pinfunction "1_1") (pintype "passive"))
    )
    (net (code "5") (name "+SYSV") (class "Default")
      (node (ref "F1") (pin "1") (pinfunction "1_1") (pintype "passive"))
    )
    (net (code "6") (name "/+PSRC1") (class "Default")
      (node (ref "F2") (pin "1") (pinfunction "1_1") (pintype "passive"))
    )
    (net (code "7") (name "/+V1W") (class "Default")
      (node (ref "C82") (pin "1") (pinfunction "1_1") (pintype "passive"))
      (node (ref "R49") (pin "1") (pinfunction "1_1") (pintype "passive"))
      (node (ref "X6") (pin "2") (pinfunction "2_2") (pintype "passive"))
    )
    (net (code "8") (name "/1W") (class "Default")
      (node (ref "R55") (pin "1") (pinfunction "1_1") (pintype "passive"))
      (node (ref "X6") (pin "1") (pinfunction "1_1") (pintype "passive"))
    )
    (net (code "9") (name "/1WRX") (class "Default")
      (node (ref "Q10") (pin "3") (pinfunction "D_3") (pintype "passive"))
      (node (ref "R50") (pin "2") (pinfunction "2_2") (pintype "passive"))
    )
    (net (code "10") (name "/1WTX") (class "Default")
      (node (ref "R57") (pin "1") (pinfunction "1_1") (pintype "passive"))
    )
    (net (code "11") (name "/CAN0H") (class "Default")
      (node (ref "E4") (pin "2") (pinfunction "2_2") (pintype "passive"))
      (node (ref "J3") (pin "2") (pinfunction "2_2") (pintype "passive"))
      (node (ref "U15") (pin "13") (pinfunction "CANH_13") (pintype "bidirectional"))
      (node (ref "X7") (pin "1") (pinfunction "1_1") (pintype "passive"))
      (node (ref "X8") (pin "1") (pinfunction "1_1") (pintype "passive"))
    )
    (net (code "12") (name "/CAN0L") (class "Default")
      (node (ref "E5") (pin "2") (pinfunction "2_2") (pintype "passive"))
      (node (ref "J4") (pin "1") (pinfunction "1_1") (pintype "passive"))
      (node (ref "U15") (pin "12") (pinfunction "CANL_12") (pintype "bidirectional"))
      (node (ref "X7") (pin "2") (pinfunction "2_2") (pintype "passive"))
      (node (ref "X8") (pin "2") (pinfunction "2_2") (pintype "passive"))
    )
    (net (code "13") (name "/CAN0_RX") (class "Default")
      (node (ref "U15") (pin "4") (pinfunction "RXD_4") (pintype "output"))
    )
    (net (code "14") (name "/CAN0_TX") (class "Default")
      (node (ref "U15") (pin "1") (pinfunction "TXD_1") (pintype "input"))
    )
    (net (code "15") (name "/CAN_EN") (class "Default")
      (node (ref "U15") (pin "6") (pinfunction "EN_6") (pintype "input"))
    )
    (net (code "16") (name "/CAN_STB") (class "Default")
      (node (ref "U15") (pin "14") (pinfunction "STB_N_14") (pintype "input"))
    )
    (net (code "17") (name "/ENC_A") (class "Default")
      (node (ref "R59") (pin "1") (pinfunction "1_1") (pintype "passive"))
      (node (ref "SW1") (pin "A") (pinfunction "A_A") (pintype "passive"))
    )
    (net (code "18") (name "/ENC_B") (class "Default")
      (node (ref "R60") (pin "1") (pinfunction "1_1") (pintype "passive"))
      (node (ref "SW1") (pin "B") (pinfunction "B_B") (pintype "passive"))
    )
    (net (code "19") (name "/ENC_SW") (class "Default")
      (node (ref "R61") (pin "1") (pinfunction "1_1") (pintype "passive"))
      (node (ref "SW1") (pin "4") (pinfunction "4_4") (pintype "passive"))
    )
    (net (code "20") (name "/LEDCAN0") (class "Default")
      (node (ref "LED1") (pin "2") (pinfunction "2_2") (pintype "passive"))
    )
    (net (code "21") (name "/LED_GR") (class "Default")
      (node (ref "U16") (pin "2") (pinfunction "A_2") (pintype "input"))
    )
    (net (code "22") (name "/LED_RD") (class "Default")
      (node (ref "U17") (pin "2") (pinfunction "A_2") (pintype "input"))
    )
    (net (code "23") (name "/OLEDV") (class "Default")
      (node (ref "DSP1") (pin "8") (pinfunction "BLK_8") (pintype "passive"))
    )
    (net (code "24") (name "/OLED_CLK") (class "Default")
      (node (ref "DSP1") (pin "3") (pinfunction "SCLK_3") (pintype "passive"))
    )
    (net (code "25") (name "/OLED_CS") (class "Default")
      (node (ref "DSP1") (pin "7") (pinfunction "CS_7") (pintype "passive"))
    )
    (net (code "26") (name "/OLED_DC") (class "Default")
      (node (ref "DSP1") (pin "6") (pinfunction "D/C_6") (pintype "passive"))
    )
    (net (code "27") (name "/OLED_DIN") (class "Default")
      (node (ref "DSP1") (pin "4") (pinfunction "MOSI_4") (pintype "passive"))
    )
    (net (code "28") (name "/OLED_RES") (class "Default")
      (node (ref "DSP1") (pin "5") (pinfunction "RES_5") (pintype "passive"))
    )
    (net (code "29") (name "/RESET") (class "Default")
      (node (ref "R54") (pin "1") (pinfunction "1_1") (pintype "passive"))
      (node (ref "X4") (pin "10") (pinfunction "10_10") (pintype "passive"))
    )
    (net (code "30") (name "/RS485A") (class "Default")
      (node (ref "E2") (pin "1") (pinfunction "1_1") (pintype "passive"))
      (node (ref "R56") (pin "2") (pinfunction "2_2") (pintype "passive"))
      (node (ref "U14") (pin "6") (pinfunction "A_6") (pintype "bidirectional"))
      (node (ref "X5") (pin "2") (pinfunction "2_2") (pintype "passive"))
    )
    (net (code "31") (name "/RS485B") (class "Default")
      (node (ref "E1") (pin "1") (pinfunction "1_1") (pintype "passive"))
      (node (ref "J2") (pin "1") (pinfunction "1_1") (pintype "passive"))
      (node (ref "U14") (pin "7") (pinfunction "B_7") (pintype "bidirectional"))
      (node (ref "X5") (pin "1") (pinfunction "1_1") (pintype "passive"))
    )
    (net (code "32") (name "/SWD_CLK") (class "Default")
      (node (ref "R52") (pin "1") (pinfunction "1_1") (pintype "passive"))
      (node (ref "X4") (pin "4") (pinfunction "4_4") (pintype "passive"))
    )
    (net (code "33") (name "/SWD_DIO") (class "Default")
      (node (ref "R48") (pin "1") (pinfunction "1_1") (pintype "passive"))
      (node (ref "X4") (pin "2") (pinfunction "2_2") (pintype "passive"))
    )
    (net (code "34") (name "/SWO") (class "Default")
      (node (ref "X4") (pin "6") (pinfunction "6_6") (pintype "passive"))
    )
    (net (code "35") (name "/UART1_RTS") (class "Default")
      (node (ref "U14") (pin "3") (pinfunction "DE_3") (pintype "input"))
    )
    (net (code "36") (name "/UART1_RX") (class "Default")
      (node (ref "U14") (pin "1") (pinfunction "RO_1") (pintype "output"))
    )
    (net (code "37") (name "/UART1_TX") (class "Default")
      (node (ref "U14") (pin "4") (pinfunction "DI_4") (pintype "input"))
    )
    (net (code "38") (name "/USB_ID") (class "Default")
      (node (ref "U20") (pin "1") (pinfunction "1_1") (pintype "passive"))
      (node (ref "X9") (pin "4") (pinfunction "ID_4") (pintype "passive"))
    )
    (net (code "39") (name "/USB_N") (class "Default")
      (node (ref "U20") (pin "3") (pinfunction "3_3") (pintype "passive"))
      (node (ref "X9") (pin "2") (pinfunction "D-_2") (pintype "bidirectional"))
    )
    (net (code "40") (name "/USB_P") (class "Default")
      (node (ref "U20") (pin "2") (pinfunction "2_2") (pintype "passive"))
      (node (ref "X9") (pin "3") (pinfunction "D+_3") (pintype "bidirectional"))
    )
    (net (code "41") (name "/USB_VBUS") (class "Default")
      (node (ref "C91") (pin "1") (pinfunction "1_1") (pintype "passive"))
      (node (ref "C92") (pin "1") (pinfunction "1_1") (pintype "passive"))
      (node (ref "L5") (pin "2") (pinfunction "2_2") (pintype "passive"))
      (node (ref "VD10") (pin "2") (pinfunction "2_2") (pintype "passive"))
    )
    (net (code "42") (name "AGND") (class "Default")
      (node (ref "B3") (pin "1") (pinfunction "1_1") (pintype "passive"))
      (node (ref "C100") (pin "1") (pinfunction "1_1") (pintype "passive"))
      (node (ref "C101") (pin "2") (pinfunction "2_2") (pintype "passive"))
      (node (ref "C102") (pin "1") (pinfunction "1_1") (pintype "passive"))
      (node (ref "C103") (pin "2") (pinfunction "2_2") (pintype "passive"))
      (node (ref "C104") (pin "2") (pinfunction "2_2") (pintype "passive"))
      (node (ref "C105") (pin "2") (pinfunction "2_2") (pintype "passive"))
      (node (ref "R68") (pin "1") (pinfunction "1_1") (pintype "passive"))
      (node (ref "U21") (pin "2") (pinfunction "GND_2") (pintype "power_in"))
      (node (ref "U22") (pin "2") (pinfunction "GND_2") (pintype "power_in"))
    )
    (net (code "43") (name "Earth") (class "Default")
      (node (ref "H1") (pin "0") (pinfunction "0_0") (pintype "passive"))
      (node (ref "H2") (pin "0") (pinfunction "0_0") (pintype "passive"))
      (node (ref "H3") (pin "0") (pinfunction "0_0") (pintype "passive"))
      (node (ref "H4") (pin "0") (pinfunction "0_0") (pintype "passive"))
      (node (ref "VD16") (pin "2") (pinfunction "A_2") (pintype "passive"))
    )
    (net (code "44") (name "GND") (class "Default")
      (node (ref "B3") (pin "2") (pinfunction "2_2") (pintype "passive"))
      (node (ref "C82") (pin "2") (pinfunction "2_2") (pintype "passive"))
      (node (ref "C83") (pin "2") (pinfunction "2_2") (pintype "passive"))
      (node (ref "C84") (pin "2") (pinfunction "2_2") (pintype "passive"))
      (node (ref "C85") (pin "2") (pinfunction "2_2") (pintype "passive"))
      (node (ref "C86") (pin "1") (pinfunction "1_1") (pintype "passive"))
      (node (ref "C87") (pin "1") (pinfunction "1_1") (pintype "passive"))
      (node (ref "C88") (pin "1") (pinfunction "1_1") (pintype "passive"))
      (node (ref "C89") (pin "1") (pinfunction "1_1") (pintype "passive"))
      (node (ref "C90") (pin "1") (pinfunction "1_1") (pintype "passive"))
      (node (ref "C91") (pin "2") (pinfunction "2_2") (pintype "passive"))
      (node (ref "C92") (pin "2") (pinfunction "2_2") (pintype "passive"))
      (node (ref "C93") (pin "2") (pinfunction "2_2") (pintype "passive"))
      (node (ref "C94") (pin "1") (pinfunction "1_1") (pintype "passive"))
      (node (ref "C95") (pin "1") (pinfunction "1_1") (pintype "passive"))
      (node (ref "C96") (pin "2") (pinfunction "2_2") (pintype "passive"))
      (node (ref "C97") (pin "1") (pinfunction "1_1") (pintype "passive"))
      (node (ref "C98") (pin "2") (pinfunction "2_2") (pintype "passive"))
      (node (ref "C99") (pin "1") (pinfunction "1_1") (pintype "passive"))
      (node (ref "DSP1") (pin "1") (pinfunction "GND_1") (pintype "passive"))
      (node (ref "E1") (pin "2") (pinfunction "2_2") (pintype "passive"))
      (node (ref "E2") (pin "2") (pinfunction "2_2") (pintype "passive"))
      (node (ref "E3") (pin "1") (pinfunction "1_1") (pintype "passive"))
      (node (ref "E4") (pin "1") (pinfunction "1_1") (pintype "passive"))
      (node (ref "E5") (pin "1") (pinfunction "1_1") (pintype "passive"))
      (node (ref "E6") (pin "1") (pinfunction "1_1") (pintype "passive"))
      (node (ref "Q10") (pin "2") (pinfunction "S_2") (pintype "passive"))
      (node (ref "Q11") (pin "2") (pinfunction "S_2") (pintype "passive"))
      (node (ref "R52") (pin "2") (pinfunction "2_2") (pintype "passive"))
      (node (ref "R59") (pin "2") (pinfunction "2_2") (pintype "passive"))
      (node (ref "R60") (pin "2") (pinfunction "2_2") (pintype "passive"))
      (node (ref "SW1") (pin "1") (pinfunction "1_1") (pintype "passive"))
      (node (ref "U14") (pin "2") (pinfunction "~{RE}_2") (pintype "input"))
      (node (ref "U14") (pin "5") (pinfunction "GND_5") (pintype "power_in"))
      (node (ref "U15") (pin "2") (pinfunction "GND_2") (pintype "power_in"))
      (node (ref "U15") (pin "9") (pinfunction "WAKE_9") (pintype "input"))
      (node (ref "U16") (pin "3") (pinfunction "GND_3") (pintype "power_in"))
      (node (ref "U17") (pin "3") (pinfunction "GND_3") (pintype "power_in"))
      (node (ref "U18") (pin "2") (pinfunction "GND_2") (pintype "power_in"))
      (node (ref "U19") (pin "4") (pinfunction "GND_4") (pintype "passive"))
      (node (ref "U19") (pin "9") (pinfunction "EP_9") (pintype "passive"))
      (node (ref "U20") (pin "7") (pinfunction "7_7") (pintype "passive"))
      (node (ref "VD13") (pin "2") (pinfunction "A_2") (pintype "passive"))
      (node (ref "VD14") (pin "2") (pinfunction "2_2") (pintype "passive"))
      (node (ref "VD15") (pin "2") (pinfunction "2_2") (pintype "passive"))
      (node (ref "VD9") (pin "1") (pinfunction "1_1") (pintype "passive"))
      (node (ref "X4") (pin "3") (pinfunction "3_3") (pintype "passive"))
      (node (ref "X4") (pin "5") (pinfunction "5_5") (pintype "passive"))
      (node (ref "X6") (pin "3") (pinfunction "3_3") (pintype "passive"))
      (node (ref "X9") (pin "0") (pinfunction "0_0") (pintype "power_in"))
      (node (ref "X9") (pin "5") (pinfunction "GND_5") (pintype "power_in"))
    )
    (net (code "45") (name "Net-(C84-Pad1)") (class "Default")
      (node (ref "C84") (pin "1") (pinfunction "1_1") (pintype "passive"))
      (node (ref "E3") (pin "2") (pinfunction "2_2") (pintype "passive"))
      (node (ref "X5") (pin "3") (pinfunction "3_3") (pintype "passive"))
    )
    (net (code "46") (name "Net-(C85-Pad1)") (class "Default")
      (node (ref "C85") (pin "1") (pinfunction "1_1") (pintype "passive"))
      (node (ref "E6") (pin "2") (pinfunction "2_2") (pintype "passive"))
      (node (ref "X7") (pin "3") (pinfunction "3_3") (pintype "passive"))
      (node (ref "X8") (pin "3") (pinfunction "3_3") (pintype "passive"))
    )
    (net (code "47") (name "Net-(F1-Pad2)") (class "Default")
      (node (ref "F1") (pin "2") (pinfunction "2_2") (pintype "passive"))
      (node (ref "VD11") (pin "2") (pinfunction "2_2") (pintype "passive"))
    )
    (net (code "48") (name "Net-(F2-Pad2)") (class "Default")
      (node (ref "F2") (pin "2") (pinfunction "2_2") (pintype "passive"))
      (node (ref "VD12") (pin "2") (pinfunction "2_2") (pintype "passive"))
    )
    (net (code "49") (name "Net-(J2-Pad2)") (class "Default")
      (node (ref "J2") (pin "2") (pinfunction "2_2") (pintype "passive"))
      (node (ref "R56") (pin "1") (pinfunction "1_1") (pintype "passive"))
    )
    (net (code "50") (name "Net-(J3-Pad1)") (class "Default")
      (node (ref "J3") (pin "1") (pinfunction "1_1") (pintype "passive"))
      (node (ref "R58") (pin "1") (pinfunction "1_1") (pintype "passive"))
    )
    (net (code "51") (name "Net-(J4-Pad2)") (class "Default")
      (node (ref "J4") (pin "2") (pinfunction "2_2") (pintype "passive"))
      (node (ref "R62") (pin "2") (pinfunction "2_2") (pintype "passive"))
    )
    (net (code "52") (name "Net-(LED1-Pad1)") (class "Default")
      (node (ref "LED1") (pin "1") (pinfunction "1_1") (pintype "passive"))
      (node (ref "R65") (pin "1") (pinfunction "1_1") (pintype "passive"))
    )
    (net (code "53") (name "Net-(Q10-G)") (class "Default")
      (node (ref "Q10") (pin "1") (pinfunction "G_1") (pintype "passive"))
      (node (ref "R53") (pin "1") (pinfunction "1_1") (pintype "passive"))
    )
    (net (code "54") (name "Net-(Q11-D)") (class "Default")
      (node (ref "Q11") (pin "3") (pinfunction "D_3") (pintype "passive"))
      (node (ref "R51") (pin "2") (pinfunction "2_2") (pintype "passive"))
      (node (ref "R53") (pin "2") (pinfunction "2_2") (pintype "passive"))
      (node (ref "R55") (pin "2") (pinfunction "2_2") (pintype "passive"))
      (node (ref "VD9") (pin "3") (pinfunction "3_3") (pintype "passive"))
    )
    (net (code "55") (name "Net-(Q11-G)") (class "Default")
      (node (ref "Q11") (pin "1") (pinfunction "G_1") (pintype "passive"))
      (node (ref "R57") (pin "2") (pinfunction "2_2") (pintype "passive"))
    )
    (net (code "56") (name "Net-(R63-Pad2)") (class "Default")
      (node (ref "R63") (pin "2") (pinfunction "2_2") (pintype "passive"))
      (node (ref "SW1") (pin "2") (pinfunction "2_2") (pintype "passive"))
    )
    (net (code "57") (name "Net-(R64-Pad2)") (class "Default")
      (node (ref "R64") (pin "2") (pinfunction "2_2") (pintype "passive"))
      (node (ref "SW1") (pin "3") (pinfunction "3_3") (pintype "passive"))
    )
    (net (code "58") (name "Net-(U15-SPLIT)") (class "Default")
      (node (ref "C87") (pin "2") (pinfunction "2_2") (pintype "passive"))
      (node (ref "R58") (pin "2") (pinfunction "2_2") (pintype "passive"))
      (node (ref "R62") (pin "1") (pinfunction "1_1") (pintype "passive"))
      (node (ref "U15") (pin "11") (pinfunction "SPLIT_11") (pintype "passive"))
    )
    (net (code "59") (name "Net-(U16-Y)") (class "Default")
      (node (ref "R63") (pin "1") (pinfunction "1_1") (pintype "passive"))
      (node (ref "U16") (pin "4") (pinfunction "Y_4") (pintype "open_collector"))
    )
    (net (code "60") (name "Net-(U17-Y)") (class "Default")
      (node (ref "R64") (pin "1") (pinfunction "1_1") (pintype "passive"))
      (node (ref "U17") (pin "4") (pinfunction "Y_4") (pintype "open_collector"))
    )
    (net (code "61") (name "Net-(U21-BYP)") (class "Default")
      (node (ref "C101") (pin "1") (pinfunction "1_1") (pintype "passive"))
      (node (ref "U21") (pin "4") (pinfunction "BYP_4") (pintype "power_in"))
    )
    (net (code "62") (name "Net-(U21-EN)") (class "Default")
      (node (ref "C100") (pin "2") (pinfunction "2_2") (pintype "passive"))
      (node (ref "L6") (pin "2") (pinfunction "2_2") (pintype "passive"))
      (node (ref "U21") (pin "1") (pinfunction "IN_1") (pintype "power_in"))
      (node (ref "U21") (pin "3") (pinfunction "EN_3") (pintype "power_in"))
    )
    (net (code "63") (name "Net-(U22-IN+)") (class "Default")
      (node (ref "C105") (pin "1") (pinfunction "1_1") (pintype "passive"))
      (node (ref "R66") (pin "1") (pinfunction "1_1") (pintype "passive"))
      (node (ref "R68") (pin "2") (pinfunction "2_2") (pintype "passive"))
      (node (ref "U22") (pin "3") (pinfunction "IN+_3") (pintype "passive"))
    )
    (net (code "64") (name "Net-(U22-IN-)") (class "Default")
      (node (ref "R67") (pin "2") (pinfunction "2_2") (pintype "passive"))
      (node (ref "U22") (pin "1") (pinfunction "OUT_1") (pintype "passive"))
      (node (ref "U22") (pin "4") (pinfunction "IN-_4") (pintype "passive"))
    )
    (net (code "65") (name "Net-(X9-VBUS)") (class "Default")
      (node (ref "C93") (pin "1") (pinfunction "1_1") (pintype "passive"))
      (node (ref "L5") (pin "1") (pinfunction "1_1") (pintype "passive"))
      (node (ref "U20") (pin "6") (pinfunction "6_6") (pintype "passive"))
      (node (ref "X9") (pin "1") (pinfunction "VBUS_1") (pintype "power_in"))
    )
    (net (code "66") (name "PGND") (class "Default")
      (node (ref "VD16") (pin "1") (pinfunction "C_1") (pintype "passive"))
    )
    (net (code "67") (name "VREF_1.65V") (class "Default")
      (node (ref "C104") (pin "1") (pinfunction "1_1") (pintype "passive"))
      (node (ref "R67") (pin "1") (pinfunction "1_1") (pintype "passive"))
    )
    (net (code "68") (name "unconnected-(U15-ERR_N-Pad8)") (class "Default")
      (node (ref "U15") (pin "8") (pinfunction "ERR_N_8") (pintype "bidirectional"))
    )
    (net (code "69") (name "unconnected-(U15-INH-Pad7)") (class "Default")
      (node (ref "U15") (pin "7") (pinfunction "INH_7") (pintype "bidirectional"))
    )
    (net (code "70") (name "unconnected-(X4-Pad7)") (class "Default")
      (node (ref "X4") (pin "7") (pinfunction "7_7") (pintype "passive"))
    )
    (net (code "71") (name "unconnected-(X4-Pad8)") (class "Default")
      (node (ref "X4") (pin "8") (pinfunction "8_8") (pintype "passive"))
    )
    (net (code "72") (name "unconnected-(X4-Pad9)") (class "Default")
      (node (ref "X4") (pin "9") (pinfunction "9_9") (pintype "passive"))
    )
  )
)
